# psu.net
KiCad netlist of a schematic drawn in EAGLE
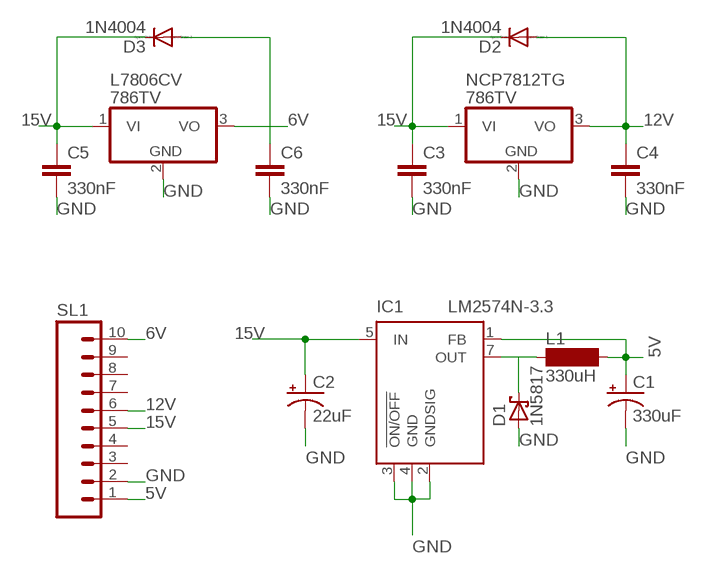
[diagram p0: schematic, sheet 1]

(export (version "E")
  (design (tool "Eeschema 10.0.6"))
  (components
    (comp (ref "C1")
      (value "330uF")
      (footprint "eagle-import:E5-8,5")
      (libsource (lib "eagle-import") (part "CPOL-USE5-8.5"))
    )
    (comp (ref "C2")
      (value "22uF")
      (footprint "eagle-import:E5-5")
      (libsource (lib "eagle-import") (part "CPOL-USE5-5"))
    )
    (comp (ref "C3")
      (value "330nF")
      (footprint "eagle-import:C050-030X075")
      (libsource (lib "eagle-import") (part "C-EU050-030X075"))
    )
    (comp (ref "C4")
      (value "330nF")
      (footprint "eagle-import:C050-030X075")
      (libsource (lib "eagle-import") (part "C-EU050-030X075"))
    )
    (comp (ref "C5")
      (value "330nF")
      (footprint "eagle-import:C050-030X075")
      (libsource (lib "eagle-import") (part "C-EU050-030X075"))
    )
    (comp (ref "C6")
      (value "330nF")
      (footprint "eagle-import:C050-030X075")
      (libsource (lib "eagle-import") (part "C-EU050-030X075"))
    )
    (comp (ref "D1")
      (value "1N5817")
      (footprint "eagle-import:DO41-10")
      (libsource (lib "eagle-import") (part "BYV10"))
    )
    (comp (ref "D2")
      (value "1N4004")
      (footprint "eagle-import:DO41-10")
      (libsource (lib "eagle-import") (part "1N4004"))
    )
    (comp (ref "D3")
      (value "1N4004")
      (footprint "eagle-import:DO41-10")
      (libsource (lib "eagle-import") (part "1N4004"))
    )
    (comp (ref "IC1")
      (value "LM2574N-3.3")
      (footprint "eagle-import:DIL08")
      (libsource (lib "eagle-import") (part "LM2574?-N3.3"))
    )
    (comp (ref "L1")
      (value "330uH")
      (footprint "eagle-import:BS11")
      (libsource (lib "eagle-import") (part "BS11"))
    )
    (comp (ref "L7806CV")
      (value "786TV")
      (footprint "eagle-import:TO220V")
      (libsource (lib "eagle-import") (part "78TV6"))
    )
    (comp (ref "NCP7812TG")
      (value "786TV")
      (footprint "eagle-import:TO220V")
      (libsource (lib "eagle-import") (part "78TV6"))
    )
    (comp (ref "SL1")
      (value "M10")
      (footprint "eagle-import:10P")
      (libsource (lib "eagle-import") (part "M10"))
    )
  )
  (nets
    (net (code "1") (name "/5V") (class "Default")
      (node (ref "C1") (pin "+") (pinfunction "+_+") (pintype "passive"))
      (node (ref "IC1") (pin "1") (pinfunction "FB_1") (pintype "input"))
      (node (ref "L1") (pin "2") (pinfunction "2_2") (pintype "passive"))
      (node (ref "SL1") (pin "1") (pinfunction "1_1") (pintype "passive"))
    )
    (net (code "2") (name "/6V") (class "Default")
      (node (ref "C6") (pin "1") (pinfunction "1_1") (pintype "passive"))
      (node (ref "D3") (pin "A") (pinfunction "A_A") (pintype "passive"))
      (node (ref "L7806CV") (pin "3") (pinfunction "VO_3") (pintype "passive"))
      (node (ref "SL1") (pin "10") (pinfunction "10_10") (pintype "passive"))
    )
    (net (code "3") (name "/12V") (class "Default")
      (node (ref "C4") (pin "1") (pinfunction "1_1") (pintype "passive"))
      (node (ref "D2") (pin "A") (pinfunction "A_A") (pintype "passive"))
      (node (ref "NCP7812TG") (pin "3") (pinfunction "VO_3") (pintype "passive"))
      (node (ref "SL1") (pin "6") (pinfunction "6_6") (pintype "passive"))
    )
    (net (code "4") (name "/15V") (class "Default")
      (node (ref "C2") (pin "+") (pinfunction "+_+") (pintype "passive"))
      (node (ref "C3") (pin "1") (pinfunction "1_1") (pintype "passive"))
      (node (ref "C5") (pin "1") (pinfunction "1_1") (pintype "passive"))
      (node (ref "D2") (pin "C") (pinfunction "C_C") (pintype "passive"))
      (node (ref "D3") (pin "C") (pinfunction "C_C") (pintype "passive"))
      (node (ref "IC1") (pin "5") (pinfunction "IN_5") (pintype "input"))
      (node (ref "L7806CV") (pin "1") (pinfunction "VI_1") (pintype "input"))
      (node (ref "NCP7812TG") (pin "1") (pinfunction "VI_1") (pintype "input"))
      (node (ref "SL1") (pin "5") (pinfunction "5_5") (pintype "passive"))
    )
    (net (code "5") (name "/GND") (class "Default")
      (node (ref "C1") (pin "-") (pinfunction "-_-") (pintype "passive"))
      (node (ref "C2") (pin "-") (pinfunction "-_-") (pintype "passive"))
      (node (ref "C3") (pin "2") (pinfunction "2_2") (pintype "passive"))
      (node (ref "C4") (pin "2") (pinfunction "2_2") (pintype "passive"))
      (node (ref "C5") (pin "2") (pinfunction "2_2") (pintype "passive"))
      (node (ref "C6") (pin "2") (pinfunction "2_2") (pintype "passive"))
      (node (ref "D1") (pin "A") (pinfunction "A_A") (pintype "passive"))
      (node (ref "IC1") (pin "2") (pinfunction "GNDSIG_2") (pintype "input"))
      (node (ref "IC1") (pin "3") (pinfunction "~{ON/OFF}_3") (pintype "input"))
      (node (ref "IC1") (pin "4") (pinfunction "GND_4") (pintype "power_in"))
      (node (ref "L7806CV") (pin "2") (pinfunction "GND_2") (pintype "passive"))
      (node (ref "NCP7812TG") (pin "2") (pinfunction "GND_2") (pintype "passive"))
      (node (ref "SL1") (pin "2") (pinfunction "2_2") (pintype "passive"))
    )
    (net (code "6") (name "Net-(IC1-OUT)") (class "Default")
      (node (ref "D1") (pin "C") (pinfunction "C_C") (pintype "passive"))
      (node (ref "IC1") (pin "7") (pinfunction "OUT_7") (pintype "passive"))
      (node (ref "L1") (pin "1") (pinfunction "1_1") (pintype "passive"))
    )
    (net (code "7") (name "unconnected-(SL1-Pad3)") (class "Default")
      (node (ref "SL1") (pin "3") (pinfunction "3_3") (pintype "passive"))
    )
    (net (code "8") (name "unconnected-(SL1-Pad4)") (class "Default")
      (node (ref "SL1") (pin "4") (pinfunction "4_4") (pintype "passive"))
    )
    (net (code "9") (name "unconnected-(SL1-Pad7)") (class "Default")
      (node (ref "SL1") (pin "7") (pinfunction "7_7") (pintype "passive"))
    )
    (net (code "10") (name "unconnected-(SL1-Pad8)") (class "Default")
      (node (ref "SL1") (pin "8") (pinfunction "8_8") (pintype "passive"))
    )
    (net (code "11") (name "unconnected-(SL1-Pad9)") (class "Default")
      (node (ref "SL1") (pin "9") (pinfunction "9_9") (pintype "passive"))
    )
  )
)
